# M650D.net
KiCad netlist of a schematic drawn in EAGLE
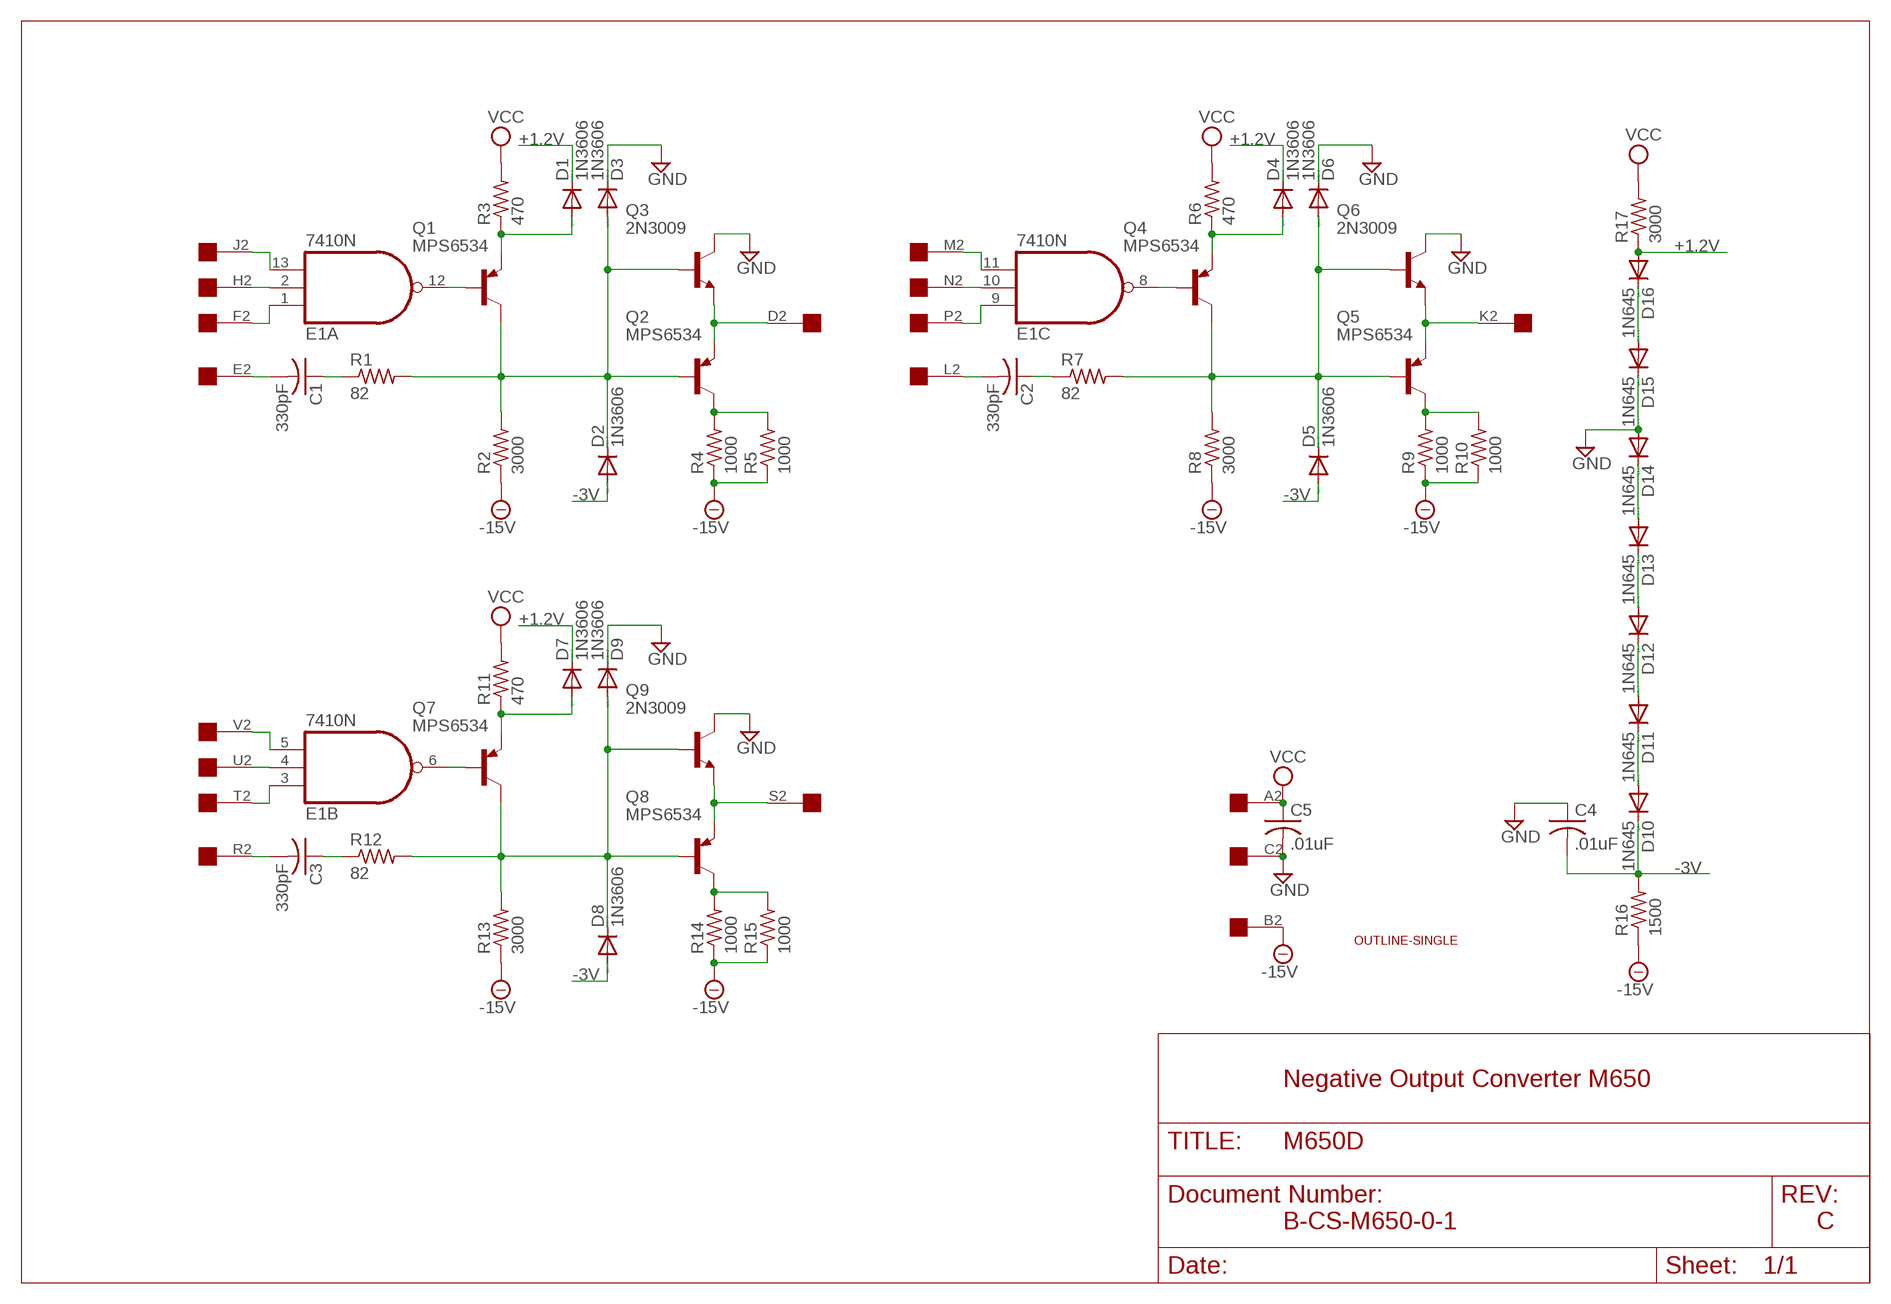
[diagram p0: schematic, sheet 1]

(export (version "E")
  (design (tool "Eeschema 10.0.6"))
  (components
    (comp (ref "C1")
      (value "330pF")
      (footprint "eagle-import:C050-025X075")
      (libsource (lib "eagle-import") (part "C-US050-025X075"))
    )
    (comp (ref "C2")
      (value "330pF")
      (footprint "eagle-import:C050-025X075")
      (libsource (lib "eagle-import") (part "C-US050-025X075"))
    )
    (comp (ref "C3")
      (value "330pF")
      (footprint "eagle-import:C050-025X075")
      (libsource (lib "eagle-import") (part "C-US050-025X075"))
    )
    (comp (ref "C4")
      (value ".01uF")
      (footprint "eagle-import:C050-025X075")
      (libsource (lib "eagle-import") (part "C-US050-025X075"))
    )
    (comp (ref "C5")
      (value ".01uF")
      (footprint "eagle-import:C050-025X075")
      (libsource (lib "eagle-import") (part "C-US050-025X075"))
    )
    (comp (ref "D1")
      (value "1N3606")
      (footprint "eagle-import:DO35-10")
      (libsource (lib "eagle-import") (part "1N4148DO35-10"))
    )
    (comp (ref "D2")
      (value "1N3606")
      (footprint "eagle-import:DO35-10")
      (libsource (lib "eagle-import") (part "1N4148DO35-10"))
    )
    (comp (ref "D3")
      (value "1N3606")
      (footprint "eagle-import:DO35-10")
      (libsource (lib "eagle-import") (part "1N4148DO35-10"))
    )
    (comp (ref "D4")
      (value "1N3606")
      (footprint "eagle-import:DO35-10")
      (libsource (lib "eagle-import") (part "1N4148DO35-10"))
    )
    (comp (ref "D5")
      (value "1N3606")
      (footprint "eagle-import:DO35-10")
      (libsource (lib "eagle-import") (part "1N4148DO35-10"))
    )
    (comp (ref "D6")
      (value "1N3606")
      (footprint "eagle-import:DO35-10")
      (libsource (lib "eagle-import") (part "1N4148DO35-10"))
    )
    (comp (ref "D7")
      (value "1N3606")
      (footprint "eagle-import:DO35-10")
      (libsource (lib "eagle-import") (part "1N4148DO35-10"))
    )
    (comp (ref "D8")
      (value "1N3606")
      (footprint "eagle-import:DO35-10")
      (libsource (lib "eagle-import") (part "1N4148DO35-10"))
    )
    (comp (ref "D9")
      (value "1N3606")
      (footprint "eagle-import:DO35-10")
      (libsource (lib "eagle-import") (part "1N4148DO35-10"))
    )
    (comp (ref "D10")
      (value "1N645")
      (footprint "eagle-import:DO35-10")
      (libsource (lib "eagle-import") (part "1N4148DO35-10"))
    )
    (comp (ref "D11")
      (value "1N645")
      (footprint "eagle-import:DO35-10")
      (libsource (lib "eagle-import") (part "1N4148DO35-10"))
    )
    (comp (ref "D12")
      (value "1N645")
      (footprint "eagle-import:DO35-10")
      (libsource (lib "eagle-import") (part "1N4148DO35-10"))
    )
    (comp (ref "D13")
      (value "1N645")
      (footprint "eagle-import:DO35-10")
      (libsource (lib "eagle-import") (part "1N4148DO35-10"))
    )
    (comp (ref "D14")
      (value "1N645")
      (footprint "eagle-import:DO35-10")
      (libsource (lib "eagle-import") (part "1N4148DO35-10"))
    )
    (comp (ref "D15")
      (value "1N645")
      (footprint "eagle-import:DO35-10")
      (libsource (lib "eagle-import") (part "1N4148DO35-10"))
    )
    (comp (ref "D16")
      (value "1N645")
      (footprint "eagle-import:DO35-10")
      (libsource (lib "eagle-import") (part "1N4148DO35-10"))
    )
    (comp (ref "E1")
      (value "7410N")
      (footprint "eagle-import:DIL14")
      (libsource (lib "eagle-import") (part "7410N"))
    )
    (comp (ref "Q1")
      (value "MPS6534")
      (footprint "eagle-import:TO39")
      (libsource (lib "eagle-import") (part "2N5415"))
    )
    (comp (ref "Q2")
      (value "MPS6534")
      (footprint "eagle-import:TO39")
      (libsource (lib "eagle-import") (part "2N5415"))
    )
    (comp (ref "Q3")
      (value "2N3009")
      (footprint "eagle-import:TO5")
      (libsource (lib "eagle-import") (part "2N2219"))
    )
    (comp (ref "Q4")
      (value "MPS6534")
      (footprint "eagle-import:TO39")
      (libsource (lib "eagle-import") (part "2N5415"))
    )
    (comp (ref "Q5")
      (value "MPS6534")
      (footprint "eagle-import:TO39")
      (libsource (lib "eagle-import") (part "2N5415"))
    )
    (comp (ref "Q6")
      (value "2N3009")
      (footprint "eagle-import:TO5")
      (libsource (lib "eagle-import") (part "2N2219"))
    )
    (comp (ref "Q7")
      (value "MPS6534")
      (footprint "eagle-import:TO39")
      (libsource (lib "eagle-import") (part "2N5415"))
    )
    (comp (ref "Q8")
      (value "MPS6534")
      (footprint "eagle-import:TO39")
      (libsource (lib "eagle-import") (part "2N5415"))
    )
    (comp (ref "Q9")
      (value "2N3009")
      (footprint "eagle-import:TO5")
      (libsource (lib "eagle-import") (part "2N2219"))
    )
    (comp (ref "R1")
      (value "82")
      (footprint "eagle-import:0207_10")
      (libsource (lib "eagle-import") (part "R-US_0207/10"))
    )
    (comp (ref "R2")
      (value "3000")
      (footprint "eagle-import:0207_10")
      (libsource (lib "eagle-import") (part "R-US_0207/10"))
    )
    (comp (ref "R3")
      (value "470")
      (footprint "eagle-import:0207_10")
      (libsource (lib "eagle-import") (part "R-US_0207/10"))
    )
    (comp (ref "R4")
      (value "1000")
      (footprint "eagle-import:0207_10")
      (libsource (lib "eagle-import") (part "R-US_0207/10"))
    )
    (comp (ref "R5")
      (value "1000")
      (footprint "eagle-import:0207_10")
      (libsource (lib "eagle-import") (part "R-US_0207/10"))
    )
    (comp (ref "R6")
      (value "470")
      (footprint "eagle-import:0207_10")
      (libsource (lib "eagle-import") (part "R-US_0207/10"))
    )
    (comp (ref "R7")
      (value "82")
      (footprint "eagle-import:0207_10")
      (libsource (lib "eagle-import") (part "R-US_0207/10"))
    )
    (comp (ref "R8")
      (value "3000")
      (footprint "eagle-import:0207_10")
      (libsource (lib "eagle-import") (part "R-US_0207/10"))
    )
    (comp (ref "R9")
      (value "1000")
      (footprint "eagle-import:0207_10")
      (libsource (lib "eagle-import") (part "R-US_0207/10"))
    )
    (comp (ref "R10")
      (value "1000")
      (footprint "eagle-import:0207_10")
      (libsource (lib "eagle-import") (part "R-US_0207/10"))
    )
    (comp (ref "R11")
      (value "470")
      (footprint "eagle-import:0207_10")
      (libsource (lib "eagle-import") (part "R-US_0207/10"))
    )
    (comp (ref "R12")
      (value "82")
      (footprint "eagle-import:0207_10")
      (libsource (lib "eagle-import") (part "R-US_0207/10"))
    )
    (comp (ref "R13")
      (value "3000")
      (footprint "eagle-import:0207_10")
      (libsource (lib "eagle-import") (part "R-US_0207/10"))
    )
    (comp (ref "R14")
      (value "1000")
      (footprint "eagle-import:0207_10")
      (libsource (lib "eagle-import") (part "R-US_0207/10"))
    )
    (comp (ref "R15")
      (value "1000")
      (footprint "eagle-import:0207_10")
      (libsource (lib "eagle-import") (part "R-US_0207/10"))
    )
    (comp (ref "R16")
      (value "1500")
      (footprint "eagle-import:0207_10")
      (libsource (lib "eagle-import") (part "R-US_0207/10"))
    )
    (comp (ref "R17")
      (value "3000")
      (footprint "eagle-import:0207_10")
      (libsource (lib "eagle-import") (part "R-US_0207/10"))
    )
    (comp (ref "U$1")
      (value "OUTLINE-SINGLE")
      (footprint "eagle-import:SINGLE")
      (libsource (lib "eagle-import") (part "OUTLINE-SINGLE"))
    )
    (comp (ref "U$3")
      (value "EDGE-1")
      (footprint "eagle-import:EDGE-CON1")
      (libsource (lib "eagle-import") (part "EDGE-1"))
    )
  )
  (nets
    (net (code "1") (name "-15V") (class "Default")
      (node (ref "R10") (pin "1") (pinfunction "1_1") (pintype "passive"))
      (node (ref "R13") (pin "1") (pinfunction "1_1") (pintype "passive"))
      (node (ref "R14") (pin "1") (pinfunction "1_1") (pintype "passive"))
      (node (ref "R15") (pin "1") (pinfunction "1_1") (pintype "passive"))
      (node (ref "R16") (pin "1") (pinfunction "1_1") (pintype "passive"))
      (node (ref "R2") (pin "1") (pinfunction "1_1") (pintype "passive"))
      (node (ref "R4") (pin "1") (pinfunction "1_1") (pintype "passive"))
      (node (ref "R5") (pin "1") (pinfunction "1_1") (pintype "passive"))
      (node (ref "R8") (pin "1") (pinfunction "1_1") (pintype "passive"))
      (node (ref "R9") (pin "1") (pinfunction "1_1") (pintype "passive"))
      (node (ref "U$3") (pin "B2") (pinfunction "1_B2") (pintype "bidirectional"))
    )
    (net (code "2") (name "/+1.2V") (class "Default")
      (node (ref "D1") (pin "C") (pinfunction "C_C") (pintype "passive"))
      (node (ref "D16") (pin "A") (pinfunction "A_A") (pintype "passive"))
      (node (ref "D4") (pin "C") (pinfunction "C_C") (pintype "passive"))
      (node (ref "D7") (pin "C") (pinfunction "C_C") (pintype "passive"))
      (node (ref "R17") (pin "1") (pinfunction "1_1") (pintype "passive"))
    )
    (net (code "3") (name "/-3V") (class "Default")
      (node (ref "C4") (pin "2") (pinfunction "2_2") (pintype "passive"))
      (node (ref "D10") (pin "C") (pinfunction "C_C") (pintype "passive"))
      (node (ref "D2") (pin "A") (pinfunction "A_A") (pintype "passive"))
      (node (ref "D5") (pin "A") (pinfunction "A_A") (pintype "passive"))
      (node (ref "D8") (pin "A") (pinfunction "A_A") (pintype "passive"))
      (node (ref "R16") (pin "2") (pinfunction "2_2") (pintype "passive"))
    )
    (net (code "4") (name "GND") (class "Default")
      (node (ref "C4") (pin "1") (pinfunction "1_1") (pintype "passive"))
      (node (ref "C5") (pin "2") (pinfunction "2_2") (pintype "passive"))
      (node (ref "D14") (pin "A") (pinfunction "A_A") (pintype "passive"))
      (node (ref "D15") (pin "C") (pinfunction "C_C") (pintype "passive"))
      (node (ref "D3") (pin "C") (pinfunction "C_C") (pintype "passive"))
      (node (ref "D6") (pin "C") (pinfunction "C_C") (pintype "passive"))
      (node (ref "D9") (pin "C") (pinfunction "C_C") (pintype "passive"))
      (node (ref "Q3") (pin "3") (pinfunction "C_3") (pintype "passive"))
      (node (ref "Q6") (pin "3") (pinfunction "C_3") (pintype "passive"))
      (node (ref "Q9") (pin "3") (pinfunction "C_3") (pintype "passive"))
      (node (ref "U$3") (pin "C2") (pinfunction "1_C2") (pintype "bidirectional"))
    )
    (net (code "5") (name "Net-(C1-Pad1)") (class "Default")
      (node (ref "C1") (pin "1") (pinfunction "1_1") (pintype "passive"))
      (node (ref "R1") (pin "1") (pinfunction "1_1") (pintype "passive"))
    )
    (net (code "6") (name "Net-(C2-Pad1)") (class "Default")
      (node (ref "C2") (pin "1") (pinfunction "1_1") (pintype "passive"))
      (node (ref "R7") (pin "1") (pinfunction "1_1") (pintype "passive"))
    )
    (net (code "7") (name "Net-(C3-Pad1)") (class "Default")
      (node (ref "C3") (pin "1") (pinfunction "1_1") (pintype "passive"))
      (node (ref "R12") (pin "1") (pinfunction "1_1") (pintype "passive"))
    )
    (net (code "8") (name "Net-(D10-PadA)") (class "Default")
      (node (ref "D10") (pin "A") (pinfunction "A_A") (pintype "passive"))
      (node (ref "D11") (pin "C") (pinfunction "C_C") (pintype "passive"))
    )
    (net (code "9") (name "Net-(D11-PadA)") (class "Default")
      (node (ref "D11") (pin "A") (pinfunction "A_A") (pintype "passive"))
      (node (ref "D12") (pin "C") (pinfunction "C_C") (pintype "passive"))
    )
    (net (code "10") (name "Net-(D12-PadA)") (class "Default")
      (node (ref "D12") (pin "A") (pinfunction "A_A") (pintype "passive"))
      (node (ref "D13") (pin "C") (pinfunction "C_C") (pintype "passive"))
    )
    (net (code "11") (name "Net-(D13-PadA)") (class "Default")
      (node (ref "D13") (pin "A") (pinfunction "A_A") (pintype "passive"))
      (node (ref "D14") (pin "C") (pinfunction "C_C") (pintype "passive"))
    )
    (net (code "12") (name "Net-(D15-PadA)") (class "Default")
      (node (ref "D15") (pin "A") (pinfunction "A_A") (pintype "passive"))
      (node (ref "D16") (pin "C") (pinfunction "C_C") (pintype "passive"))
    )
    (net (code "13") (name "Net-(E1A-I0)") (class "Default")
      (node (ref "E1") (pin "1") (pinfunction "I0_1") (pintype "input"))
      (node (ref "U$3") (pin "F2") (pinfunction "1_F2") (pintype "bidirectional"))
    )
    (net (code "14") (name "Net-(E1A-I1)") (class "Default")
      (node (ref "E1") (pin "2") (pinfunction "I1_2") (pintype "input"))
      (node (ref "U$3") (pin "H2") (pinfunction "1_H2") (pintype "bidirectional"))
    )
    (net (code "15") (name "Net-(E1A-I2)") (class "Default")
      (node (ref "E1") (pin "13") (pinfunction "I2_13") (pintype "input"))
      (node (ref "U$3") (pin "J2") (pinfunction "1_J2") (pintype "bidirectional"))
    )
    (net (code "16") (name "Net-(E1A-O)") (class "Default")
      (node (ref "E1") (pin "12") (pinfunction "O_12") (pintype "output"))
      (node (ref "Q1") (pin "2") (pinfunction "B_2") (pintype "passive"))
    )
    (net (code "17") (name "Net-(E1B-I0)") (class "Default")
      (node (ref "E1") (pin "3") (pinfunction "I0_3") (pintype "input"))
      (node (ref "U$3") (pin "T2") (pinfunction "1_T2") (pintype "bidirectional"))
    )
    (net (code "18") (name "Net-(E1B-I1)") (class "Default")
      (node (ref "E1") (pin "4") (pinfunction "I1_4") (pintype "input"))
      (node (ref "U$3") (pin "U2") (pinfunction "1_U2") (pintype "bidirectional"))
    )
    (net (code "19") (name "Net-(E1B-I2)") (class "Default")
      (node (ref "E1") (pin "5") (pinfunction "I2_5") (pintype "input"))
      (node (ref "U$3") (pin "V2") (pinfunction "1_V2") (pintype "bidirectional"))
    )
    (net (code "20") (name "Net-(E1B-O)") (class "Default")
      (node (ref "E1") (pin "6") (pinfunction "O_6") (pintype "output"))
      (node (ref "Q7") (pin "2") (pinfunction "B_2") (pintype "passive"))
    )
    (net (code "21") (name "Net-(E1C-I0)") (class "Default")
      (node (ref "E1") (pin "9") (pinfunction "I0_9") (pintype "input"))
      (node (ref "U$3") (pin "P2") (pinfunction "1_P2") (pintype "bidirectional"))
    )
    (net (code "22") (name "Net-(E1C-I1)") (class "Default")
      (node (ref "E1") (pin "10") (pinfunction "I1_10") (pintype "input"))
      (node (ref "U$3") (pin "N2") (pinfunction "1_N2") (pintype "bidirectional"))
    )
    (net (code "23") (name "Net-(E1C-I2)") (class "Default")
      (node (ref "E1") (pin "11") (pinfunction "I2_11") (pintype "input"))
      (node (ref "U$3") (pin "M2") (pinfunction "1_M2") (pintype "bidirectional"))
    )
    (net (code "24") (name "Net-(E1C-O)") (class "Default")
      (node (ref "E1") (pin "8") (pinfunction "O_8") (pintype "output"))
      (node (ref "Q4") (pin "2") (pinfunction "B_2") (pintype "passive"))
    )
    (net (code "25") (name "Net-(Q1-C)") (class "Default")
      (node (ref "D2") (pin "C") (pinfunction "C_C") (pintype "passive"))
      (node (ref "D3") (pin "A") (pinfunction "A_A") (pintype "passive"))
      (node (ref "Q1") (pin "3") (pinfunction "C_3") (pintype "passive"))
      (node (ref "Q2") (pin "2") (pinfunction "B_2") (pintype "passive"))
      (node (ref "Q3") (pin "2") (pinfunction "B_2") (pintype "passive"))
      (node (ref "R1") (pin "2") (pinfunction "2_2") (pintype "passive"))
      (node (ref "R2") (pin "2") (pinfunction "2_2") (pintype "passive"))
    )
    (net (code "26") (name "Net-(Q1-E)") (class "Default")
      (node (ref "D1") (pin "A") (pinfunction "A_A") (pintype "passive"))
      (node (ref "Q1") (pin "1") (pinfunction "E_1") (pintype "passive"))
      (node (ref "R3") (pin "1") (pinfunction "1_1") (pintype "passive"))
    )
    (net (code "27") (name "Net-(Q2-C)") (class "Default")
      (node (ref "Q2") (pin "3") (pinfunction "C_3") (pintype "passive"))
      (node (ref "R4") (pin "2") (pinfunction "2_2") (pintype "passive"))
      (node (ref "R5") (pin "2") (pinfunction "2_2") (pintype "passive"))
    )
    (net (code "28") (name "Net-(Q2-E)") (class "Default")
      (node (ref "Q2") (pin "1") (pinfunction "E_1") (pintype "passive"))
      (node (ref "Q3") (pin "1") (pinfunction "E_1") (pintype "passive"))
      (node (ref "U$3") (pin "D2") (pinfunction "1_D2") (pintype "bidirectional"))
    )
    (net (code "29") (name "Net-(Q4-C)") (class "Default")
      (node (ref "D5") (pin "C") (pinfunction "C_C") (pintype "passive"))
      (node (ref "D6") (pin "A") (pinfunction "A_A") (pintype "passive"))
      (node (ref "Q4") (pin "3") (pinfunction "C_3") (pintype "passive"))
      (node (ref "Q5") (pin "2") (pinfunction "B_2") (pintype "passive"))
      (node (ref "Q6") (pin "2") (pinfunction "B_2") (pintype "passive"))
      (node (ref "R7") (pin "2") (pinfunction "2_2") (pintype "passive"))
      (node (ref "R8") (pin "2") (pinfunction "2_2") (pintype "passive"))
    )
    (net (code "30") (name "Net-(Q4-E)") (class "Default")
      (node (ref "D4") (pin "A") (pinfunction "A_A") (pintype "passive"))
      (node (ref "Q4") (pin "1") (pinfunction "E_1") (pintype "passive"))
      (node (ref "R6") (pin "1") (pinfunction "1_1") (pintype "passive"))
    )
    (net (code "31") (name "Net-(Q5-C)") (class "Default")
      (node (ref "Q5") (pin "3") (pinfunction "C_3") (pintype "passive"))
      (node (ref "R10") (pin "2") (pinfunction "2_2") (pintype "passive"))
      (node (ref "R9") (pin "2") (pinfunction "2_2") (pintype "passive"))
    )
    (net (code "32") (name "Net-(Q5-E)") (class "Default")
      (node (ref "Q5") (pin "1") (pinfunction "E_1") (pintype "passive"))
      (node (ref "Q6") (pin "1") (pinfunction "E_1") (pintype "passive"))
      (node (ref "U$3") (pin "K2") (pinfunction "1_K2") (pintype "bidirectional"))
    )
    (net (code "33") (name "Net-(Q7-C)") (class "Default")
      (node (ref "D8") (pin "C") (pinfunction "C_C") (pintype "passive"))
      (node (ref "D9") (pin "A") (pinfunction "A_A") (pintype "passive"))
      (node (ref "Q7") (pin "3") (pinfunction "C_3") (pintype "passive"))
      (node (ref "Q8") (pin "2") (pinfunction "B_2") (pintype "passive"))
      (node (ref "Q9") (pin "2") (pinfunction "B_2") (pintype "passive"))
      (node (ref "R12") (pin "2") (pinfunction "2_2") (pintype "passive"))
      (node (ref "R13") (pin "2") (pinfunction "2_2") (pintype "passive"))
    )
    (net (code "34") (name "Net-(Q7-E)") (class "Default")
      (node (ref "D7") (pin "A") (pinfunction "A_A") (pintype "passive"))
      (node (ref "Q7") (pin "1") (pinfunction "E_1") (pintype "passive"))
      (node (ref "R11") (pin "1") (pinfunction "1_1") (pintype "passive"))
    )
    (net (code "35") (name "Net-(Q8-C)") (class "Default")
      (node (ref "Q8") (pin "3") (pinfunction "C_3") (pintype "passive"))
      (node (ref "R14") (pin "2") (pinfunction "2_2") (pintype "passive"))
      (node (ref "R15") (pin "2") (pinfunction "2_2") (pintype "passive"))
    )
    (net (code "36") (name "Net-(Q8-E)") (class "Default")
      (node (ref "Q8") (pin "1") (pinfunction "E_1") (pintype "passive"))
      (node (ref "Q9") (pin "1") (pinfunction "E_1") (pintype "passive"))
      (node (ref "U$3") (pin "S2") (pinfunction "1_S2") (pintype "bidirectional"))
    )
    (net (code "37") (name "Net-(U$3E-1)") (class "Default")
      (node (ref "C1") (pin "2") (pinfunction "2_2") (pintype "passive"))
      (node (ref "U$3") (pin "E2") (pinfunction "1_E2") (pintype "bidirectional"))
    )
    (net (code "38") (name "Net-(U$3J-1)") (class "Default")
      (node (ref "C2") (pin "2") (pinfunction "2_2") (pintype "passive"))
      (node (ref "U$3") (pin "L2") (pinfunction "1_L2") (pintype "bidirectional"))
    )
    (net (code "39") (name "Net-(U$3N-1)") (class "Default")
      (node (ref "C3") (pin "2") (pinfunction "2_2") (pintype "passive"))
      (node (ref "U$3") (pin "R2") (pinfunction "1_R2") (pintype "bidirectional"))
    )
    (net (code "40") (name "VCC") (class "Default")
      (node (ref "C5") (pin "1") (pinfunction "1_1") (pintype "passive"))
      (node (ref "R11") (pin "2") (pinfunction "2_2") (pintype "passive"))
      (node (ref "R17") (pin "2") (pinfunction "2_2") (pintype "passive"))
      (node (ref "R3") (pin "2") (pinfunction "2_2") (pintype "passive"))
      (node (ref "R6") (pin "2") (pinfunction "2_2") (pintype "passive"))
      (node (ref "U$3") (pin "A2") (pinfunction "1_A2") (pintype "bidirectional"))
    )
  )
)
